# gluecksrad.net
KiCad netlist of a schematic drawn in EAGLE
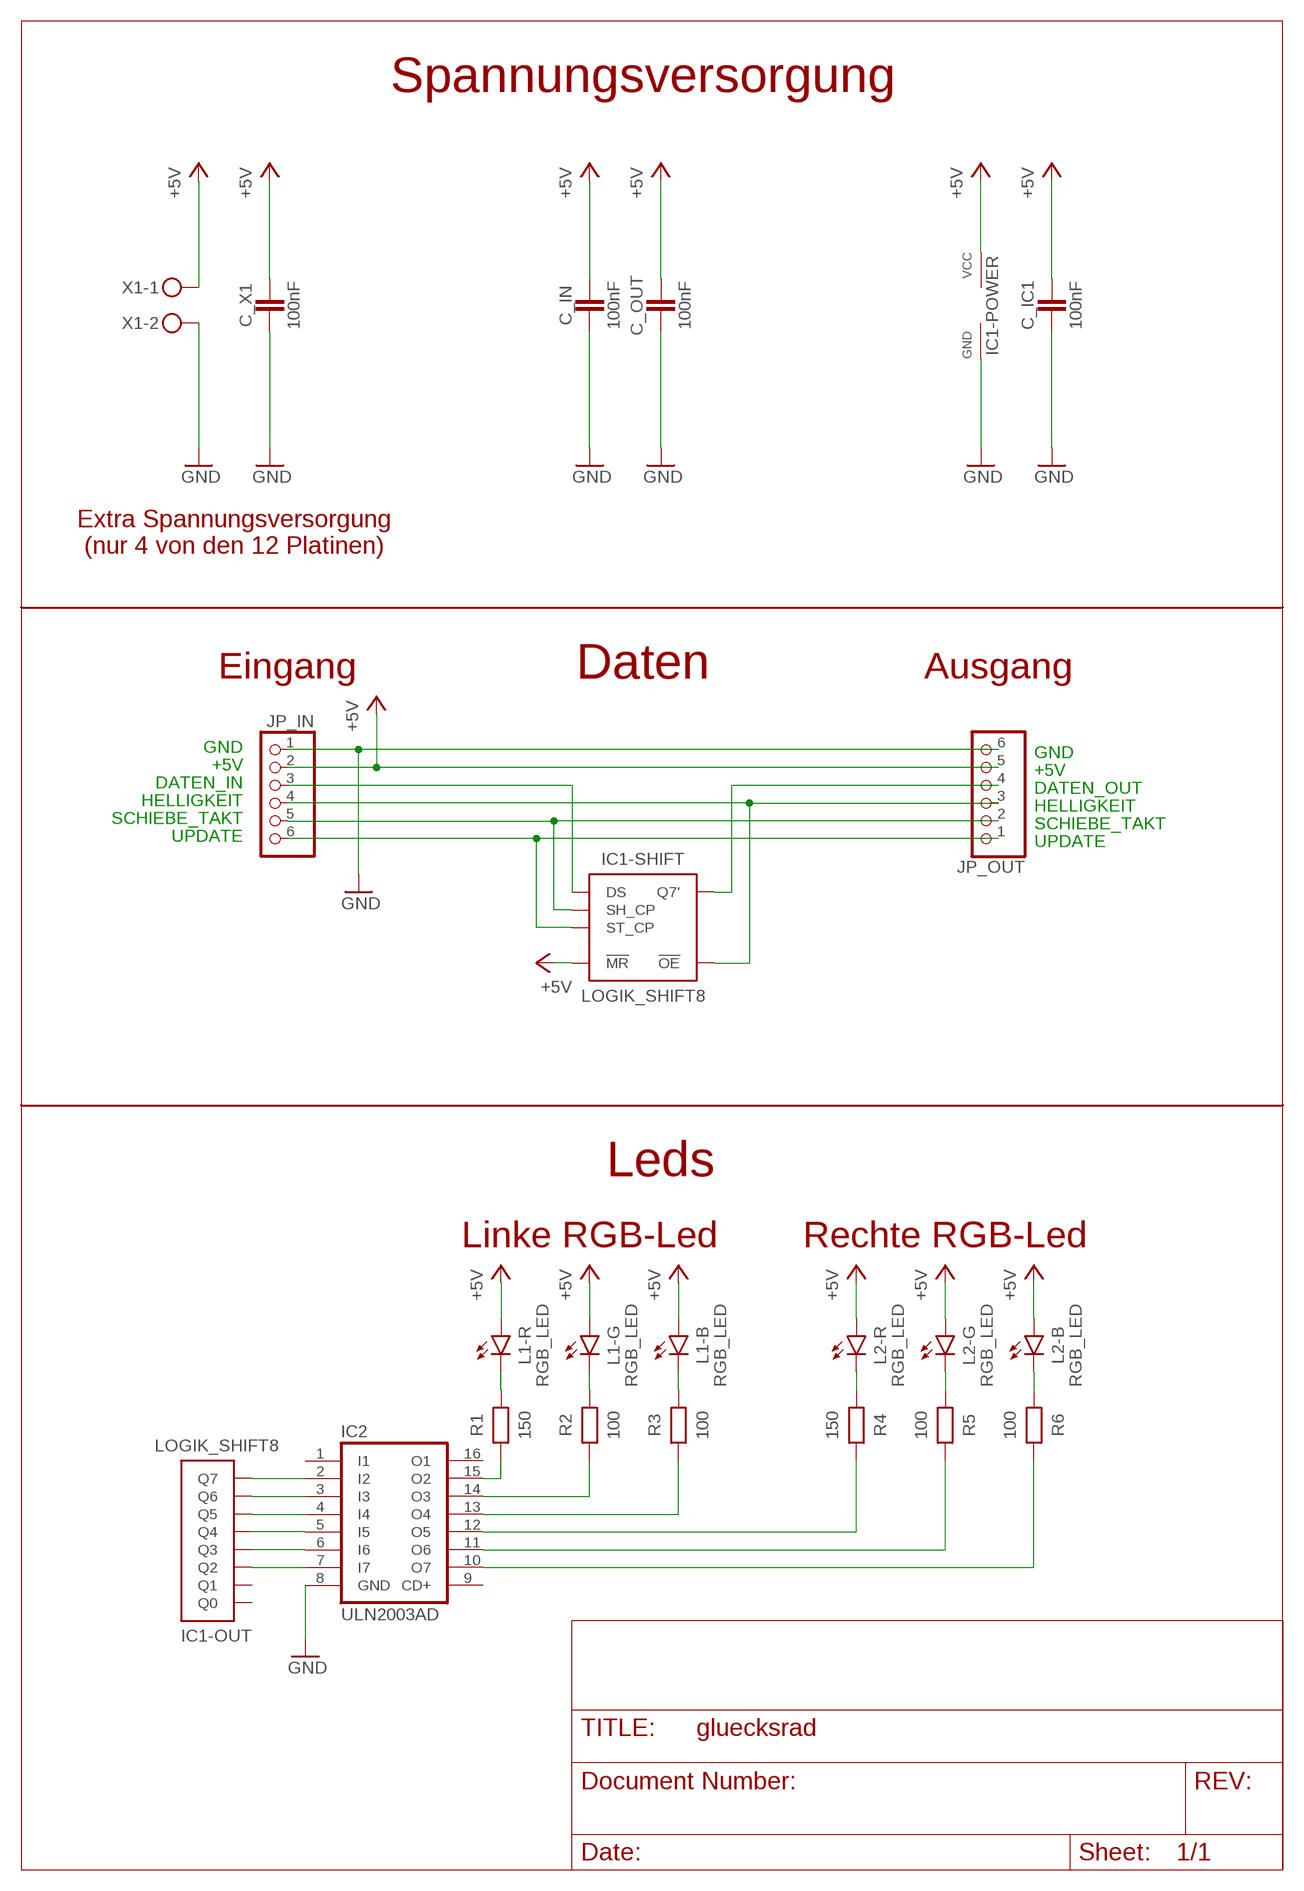
[diagram p0: schematic, sheet 1]

(export (version "E")
  (design (tool "Eeschema 10.0.6"))
  (components
    (comp (ref "C_IC1")
      (value "100nF")
      (footprint "eagle-import:C_THT_2")
      (libsource (lib "eagle-import") (part "CAPACITATOR-2,5MM"))
    )
    (comp (ref "C_IN")
      (value "100nF")
      (footprint "eagle-import:C_THT_2")
      (libsource (lib "eagle-import") (part "CAPACITATOR-2,5MM"))
    )
    (comp (ref "C_OUT")
      (value "100nF")
      (footprint "eagle-import:C_THT_2")
      (libsource (lib "eagle-import") (part "CAPACITATOR-2,5MM"))
    )
    (comp (ref "C_X1")
      (value "100nF")
      (footprint "eagle-import:C_THT_2")
      (libsource (lib "eagle-import") (part "CAPACITATOR-2,5MM"))
    )
    (comp (ref "IC1")
      (value "LOGIK_SHIFT8")
      (footprint "eagle-import:IC_SOIC16")
      (libsource (lib "eagle-import") (part "LOGIK_SHIFT8"))
    )
    (comp (ref "IC2")
      (value "ULN2003AD")
      (footprint "eagle-import:SO16")
      (libsource (lib "eagle-import") (part "ULN2003AD"))
    )
    (comp (ref "JP_IN")
      (value "PINHD-1X6/90")
      (footprint "eagle-import:1X06_90")
      (libsource (lib "eagle-import") (part "PINHD-1X6/90"))
    )
    (comp (ref "JP_OUT")
      (value "PINHD-1X6/90")
      (footprint "eagle-import:1X06_90")
      (libsource (lib "eagle-import") (part "PINHD-1X6/90"))
    )
    (comp (ref "L1")
      (value "RGB_LED")
      (footprint "eagle-import:LED_TOP_PLCC6")
      (libsource (lib "eagle-import") (part "LED_3X"))
    )
    (comp (ref "L2")
      (value "RGB_LED")
      (footprint "eagle-import:LED_TOP_PLCC6")
      (libsource (lib "eagle-import") (part "LED_3X"))
    )
    (comp (ref "R1")
      (value "150")
      (footprint "eagle-import:R_THT_4")
      (libsource (lib "eagle-import") (part "RESISTOR-10MM"))
    )
    (comp (ref "R2")
      (value "100")
      (footprint "eagle-import:R_THT_4")
      (libsource (lib "eagle-import") (part "RESISTOR-10MM"))
    )
    (comp (ref "R3")
      (value "100")
      (footprint "eagle-import:R_THT_4")
      (libsource (lib "eagle-import") (part "RESISTOR-10MM"))
    )
    (comp (ref "R4")
      (value "150")
      (footprint "eagle-import:R_THT_4")
      (libsource (lib "eagle-import") (part "RESISTOR-10MM"))
    )
    (comp (ref "R5")
      (value "100")
      (footprint "eagle-import:R_THT_4")
      (libsource (lib "eagle-import") (part "RESISTOR-10MM"))
    )
    (comp (ref "R6")
      (value "100")
      (footprint "eagle-import:R_THT_4")
      (libsource (lib "eagle-import") (part "RESISTOR-10MM"))
    )
    (comp (ref "X1")
      (value "STECKER_SPG_2")
      (footprint "eagle-import:STECKER_SPG_2")
      (libsource (lib "eagle-import") (part "STECKER_SPG_2"))
    )
  )
  (nets
    (net (code "1") (name "+5V") (class "Default")
      (node (ref "C_IC1") (pin "1") (pinfunction "1_1") (pintype "passive"))
      (node (ref "C_IN") (pin "1") (pinfunction "1_1") (pintype "passive"))
      (node (ref "C_OUT") (pin "1") (pinfunction "1_1") (pintype "passive"))
      (node (ref "C_X1") (pin "1") (pinfunction "1_1") (pintype "passive"))
      (node (ref "IC1") (pin "P$10") (pinfunction "~{MR}_P$10") (pintype "input"))
      (node (ref "IC1") (pin "P$16") (pinfunction "VCC_P$16") (pintype "power_in"))
      (node (ref "JP_IN") (pin "2") (pinfunction "2_2") (pintype "passive"))
      (node (ref "JP_OUT") (pin "5") (pinfunction "5_5") (pintype "passive"))
      (node (ref "L1") (pin "1") (pinfunction "A_1") (pintype "passive"))
      (node (ref "L1") (pin "3") (pinfunction "A_3") (pintype "passive"))
      (node (ref "L1") (pin "4") (pinfunction "A_4") (pintype "passive"))
      (node (ref "L2") (pin "1") (pinfunction "A_1") (pintype "passive"))
      (node (ref "L2") (pin "3") (pinfunction "A_3") (pintype "passive"))
      (node (ref "L2") (pin "4") (pinfunction "A_4") (pintype "passive"))
      (node (ref "X1") (pin "1") (pinfunction "KL_1") (pintype "passive"))
    )
    (net (code "2") (name "/DATEN_IN") (class "Default")
      (node (ref "IC1") (pin "P$14") (pinfunction "DS_P$14") (pintype "input"))
      (node (ref "JP_IN") (pin "3") (pinfunction "3_3") (pintype "passive"))
    )
    (net (code "3") (name "/DATEN_OUT") (class "Default")
      (node (ref "IC1") (pin "P$9") (pinfunction "Q7'_P$9") (pintype "output"))
      (node (ref "JP_OUT") (pin "4") (pinfunction "4_4") (pintype "passive"))
    )
    (net (code "4") (name "/HELLIGKEIT") (class "Default")
      (node (ref "IC1") (pin "P$13") (pinfunction "~{OE}_P$13") (pintype "input"))
      (node (ref "JP_IN") (pin "4") (pinfunction "4_4") (pintype "passive"))
      (node (ref "JP_OUT") (pin "3") (pinfunction "3_3") (pintype "passive"))
    )
    (net (code "5") (name "/SCHIEBE_TAKT") (class "Default")
      (node (ref "IC1") (pin "P$11") (pinfunction "SH_CP_P$11") (pintype "input"))
      (node (ref "JP_IN") (pin "5") (pinfunction "5_5") (pintype "passive"))
      (node (ref "JP_OUT") (pin "2") (pinfunction "2_2") (pintype "passive"))
    )
    (net (code "6") (name "/UPDATE") (class "Default")
      (node (ref "IC1") (pin "P$12") (pinfunction "ST_CP_P$12") (pintype "input"))
      (node (ref "JP_IN") (pin "6") (pinfunction "6_6") (pintype "passive"))
      (node (ref "JP_OUT") (pin "1") (pinfunction "1_1") (pintype "passive"))
    )
    (net (code "7") (name "GND") (class "Default")
      (node (ref "C_IC1") (pin "2") (pinfunction "2_2") (pintype "passive"))
      (node (ref "C_IN") (pin "2") (pinfunction "2_2") (pintype "passive"))
      (node (ref "C_OUT") (pin "2") (pinfunction "2_2") (pintype "passive"))
      (node (ref "C_X1") (pin "2") (pinfunction "2_2") (pintype "passive"))
      (node (ref "IC1") (pin "P$8") (pinfunction "GND_P$8") (pintype "power_in"))
      (node (ref "IC2") (pin "8") (pinfunction "GND_8") (pintype "power_in"))
      (node (ref "JP_IN") (pin "1") (pinfunction "1_1") (pintype "passive"))
      (node (ref "JP_OUT") (pin "6") (pinfunction "6_6") (pintype "passive"))
      (node (ref "X1") (pin "2") (pinfunction "KL_2") (pintype "passive"))
    )
    (net (code "8") (name "Net-(IC1A-Q2)") (class "Default")
      (node (ref "IC1") (pin "P$2") (pinfunction "Q2_P$2") (pintype "output"))
      (node (ref "IC2") (pin "7") (pinfunction "I7_7") (pintype "input"))
    )
    (net (code "9") (name "Net-(IC1A-Q3)") (class "Default")
      (node (ref "IC1") (pin "P$3") (pinfunction "Q3_P$3") (pintype "output"))
      (node (ref "IC2") (pin "6") (pinfunction "I6_6") (pintype "input"))
    )
    (net (code "10") (name "Net-(IC1A-Q4)") (class "Default")
      (node (ref "IC1") (pin "P$4") (pinfunction "Q4_P$4") (pintype "output"))
      (node (ref "IC2") (pin "5") (pinfunction "I5_5") (pintype "input"))
    )
    (net (code "11") (name "Net-(IC1A-Q5)") (class "Default")
      (node (ref "IC1") (pin "P$5") (pinfunction "Q5_P$5") (pintype "output"))
      (node (ref "IC2") (pin "4") (pinfunction "I4_4") (pintype "input"))
    )
    (net (code "12") (name "Net-(IC1A-Q6)") (class "Default")
      (node (ref "IC1") (pin "P$6") (pinfunction "Q6_P$6") (pintype "output"))
      (node (ref "IC2") (pin "3") (pinfunction "I3_3") (pintype "input"))
    )
    (net (code "13") (name "Net-(IC1A-Q7)") (class "Default")
      (node (ref "IC1") (pin "P$7") (pinfunction "Q7_P$7") (pintype "output"))
      (node (ref "IC2") (pin "2") (pinfunction "I2_2") (pintype "input"))
    )
    (net (code "14") (name "Net-(IC2-O2)") (class "Default")
      (node (ref "IC2") (pin "15") (pinfunction "O2_15") (pintype "open_collector"))
      (node (ref "R1") (pin "2") (pinfunction "P2_2") (pintype "passive"))
    )
    (net (code "15") (name "Net-(IC2-O3)") (class "Default")
      (node (ref "IC2") (pin "14") (pinfunction "O3_14") (pintype "open_collector"))
      (node (ref "R2") (pin "2") (pinfunction "P2_2") (pintype "passive"))
    )
    (net (code "16") (name "Net-(IC2-O4)") (class "Default")
      (node (ref "IC2") (pin "13") (pinfunction "O4_13") (pintype "open_collector"))
      (node (ref "R3") (pin "2") (pinfunction "P2_2") (pintype "passive"))
    )
    (net (code "17") (name "Net-(IC2-O5)") (class "Default")
      (node (ref "IC2") (pin "12") (pinfunction "O5_12") (pintype "open_collector"))
      (node (ref "R4") (pin "1") (pinfunction "P1_1") (pintype "passive"))
    )
    (net (code "18") (name "Net-(IC2-O6)") (class "Default")
      (node (ref "IC2") (pin "11") (pinfunction "O6_11") (pintype "open_collector"))
      (node (ref "R5") (pin "1") (pinfunction "P1_1") (pintype "passive"))
    )
    (net (code "19") (name "Net-(IC2-O7)") (class "Default")
      (node (ref "IC2") (pin "10") (pinfunction "O7_10") (pintype "open_collector"))
      (node (ref "R6") (pin "1") (pinfunction "P1_1") (pintype "passive"))
    )
    (net (code "20") (name "Net-(L1A-C)") (class "Default")
      (node (ref "L1") (pin "5") (pinfunction "C_5") (pintype "passive"))
      (node (ref "R3") (pin "1") (pinfunction "P1_1") (pintype "passive"))
    )
    (net (code "21") (name "Net-(L1B-C)") (class "Default")
      (node (ref "L1") (pin "2") (pinfunction "C_2") (pintype "passive"))
      (node (ref "R2") (pin "1") (pinfunction "P1_1") (pintype "passive"))
    )
    (net (code "22") (name "Net-(L1C-C)") (class "Default")
      (node (ref "L1") (pin "6") (pinfunction "C_6") (pintype "passive"))
      (node (ref "R1") (pin "1") (pinfunction "P1_1") (pintype "passive"))
    )
    (net (code "23") (name "Net-(L2A-C)") (class "Default")
      (node (ref "L2") (pin "5") (pinfunction "C_5") (pintype "passive"))
      (node (ref "R6") (pin "2") (pinfunction "P2_2") (pintype "passive"))
    )
    (net (code "24") (name "Net-(L2B-C)") (class "Default")
      (node (ref "L2") (pin "2") (pinfunction "C_2") (pintype "passive"))
      (node (ref "R5") (pin "2") (pinfunction "P2_2") (pintype "passive"))
    )
    (net (code "25") (name "Net-(L2C-C)") (class "Default")
      (node (ref "L2") (pin "6") (pinfunction "C_6") (pintype "passive"))
      (node (ref "R4") (pin "2") (pinfunction "P2_2") (pintype "passive"))
    )
    (net (code "26") (name "unconnected-(IC1A-Q0-PadP$15)") (class "Default")
      (node (ref "IC1") (pin "P$15") (pinfunction "Q0_P$15") (pintype "output"))
    )
    (net (code "27") (name "unconnected-(IC1A-Q1-PadP$1)") (class "Default")
      (node (ref "IC1") (pin "P$1") (pinfunction "Q1_P$1") (pintype "output"))
    )
    (net (code "28") (name "unconnected-(IC2-CD+-Pad9)") (class "Default")
      (node (ref "IC2") (pin "9") (pinfunction "CD+_9") (pintype "passive"))
    )
    (net (code "29") (name "unconnected-(IC2-I1-Pad1)") (class "Default")
      (node (ref "IC2") (pin "1") (pinfunction "I1_1") (pintype "input"))
    )
    (net (code "30") (name "unconnected-(IC2-O1-Pad16)") (class "Default")
      (node (ref "IC2") (pin "16") (pinfunction "O1_16") (pintype "open_collector"))
    )
  )
)
